# FetherV2_REV1.net
KiCad netlist of a schematic drawn in EAGLE
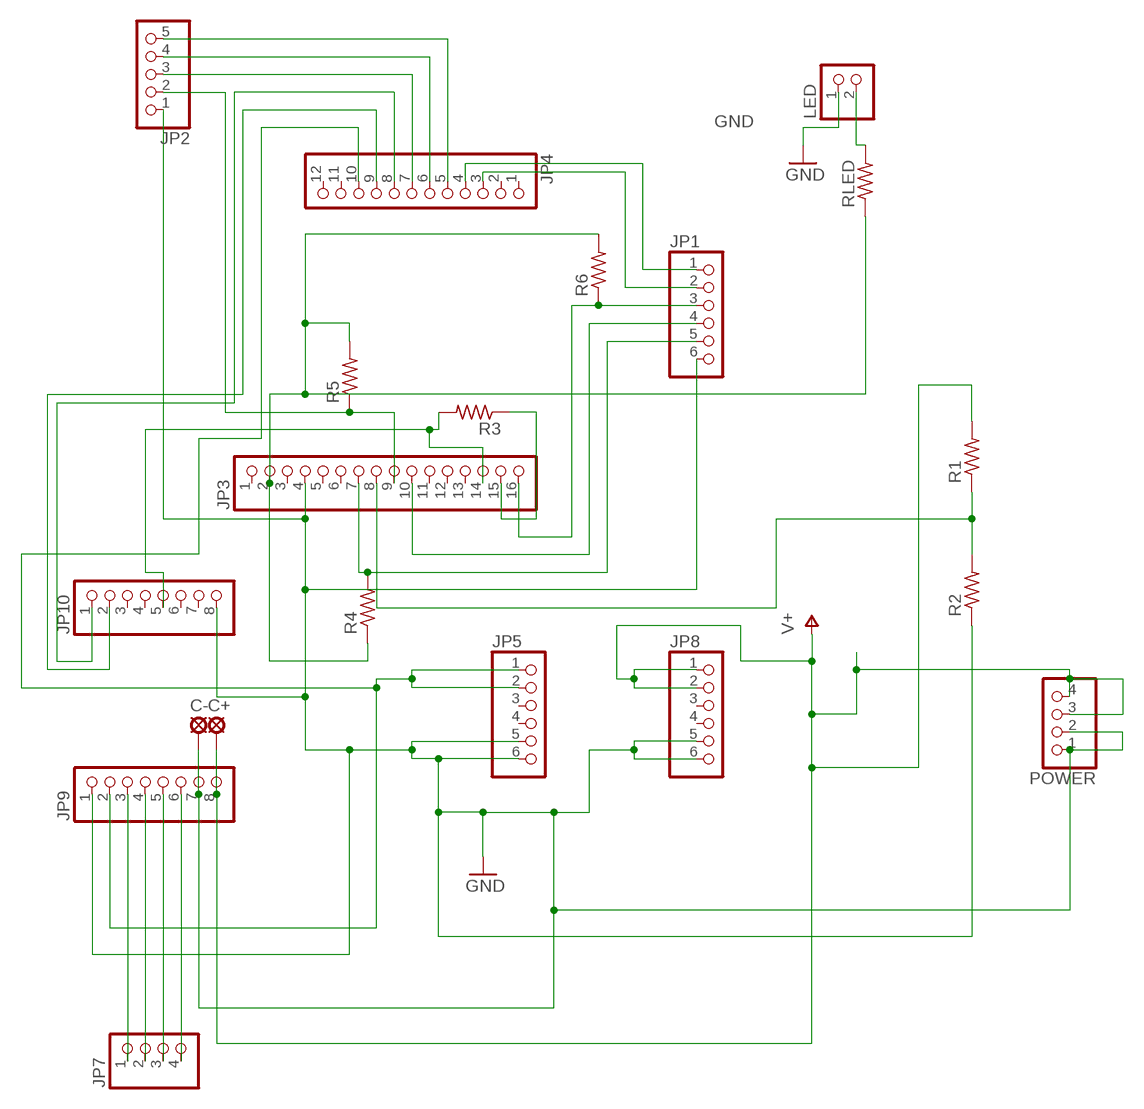
[diagram p0: schematic, sheet 1]

(export (version "E")
  (design (tool "Eeschema 10.0.6"))
  (components
    (comp (ref "C+")
      (value "SE14")
      (footprint "eagle-import:SE14")
      (libsource (lib "eagle-import") (part "SE14"))
    )
    (comp (ref "C-")
      (value "SE14")
      (footprint "eagle-import:SE14")
      (libsource (lib "eagle-import") (part "SE14"))
    )
    (comp (ref "JP1")
      (value "PINHD-1X6/90")
      (footprint "eagle-import:1X06_90")
      (libsource (lib "eagle-import") (part "PINHD-1X6/90"))
    )
    (comp (ref "JP2")
      (value "PINHD-1X5/90")
      (footprint "eagle-import:1X05_90")
      (libsource (lib "eagle-import") (part "PINHD-1X5/90"))
    )
    (comp (ref "JP3")
      (value "PINHD-1X16")
      (footprint "eagle-import:1X16")
      (libsource (lib "eagle-import") (part "PINHD-1X16"))
    )
    (comp (ref "JP4")
      (value "PINHD-1X12")
      (footprint "eagle-import:1X12")
      (libsource (lib "eagle-import") (part "PINHD-1X12"))
    )
    (comp (ref "JP5")
      (value "PINHD-1X6")
      (footprint "eagle-import:1X06")
      (libsource (lib "eagle-import") (part "PINHD-1X6"))
    )
    (comp (ref "JP7")
      (value "PINHD-1X4")
      (footprint "eagle-import:1X04")
      (libsource (lib "eagle-import") (part "PINHD-1X4"))
    )
    (comp (ref "JP8")
      (value "PINHD-1X6")
      (footprint "eagle-import:1X06")
      (libsource (lib "eagle-import") (part "PINHD-1X6"))
    )
    (comp (ref "JP9")
      (value "PINHD-1X8")
      (footprint "eagle-import:1X08")
      (libsource (lib "eagle-import") (part "PINHD-1X8"))
    )
    (comp (ref "JP10")
      (value "PINHD-1X8")
      (footprint "eagle-import:1X08")
      (libsource (lib "eagle-import") (part "PINHD-1X8"))
    )
    (comp (ref "LED")
      (value "PINHD-1X2")
      (footprint "eagle-import:1X02")
      (libsource (lib "eagle-import") (part "PINHD-1X2"))
    )
    (comp (ref "POWER")
      (value "PINHD-1X4")
      (footprint "eagle-import:1X04")
      (libsource (lib "eagle-import") (part "PINHD-1X4"))
    )
    (comp (ref "R1")
      (value "FLIPFLOP-RES")
      (footprint "eagle-import:0805-THM")
      (libsource (lib "eagle-import") (part "FLIPFLOP-RES"))
    )
    (comp (ref "R2")
      (value "FLIPFLOP-RES")
      (footprint "eagle-import:0805-THM")
      (libsource (lib "eagle-import") (part "FLIPFLOP-RES"))
    )
    (comp (ref "R3")
      (value "FLIPFLOP-RES")
      (footprint "eagle-import:0805-THM")
      (libsource (lib "eagle-import") (part "FLIPFLOP-RES"))
    )
    (comp (ref "R4")
      (value "FLIPFLOP-RES")
      (footprint "eagle-import:0805-THM")
      (libsource (lib "eagle-import") (part "FLIPFLOP-RES"))
    )
    (comp (ref "R5")
      (value "FLIPFLOP-RES")
      (footprint "eagle-import:0805-THM")
      (libsource (lib "eagle-import") (part "FLIPFLOP-RES"))
    )
    (comp (ref "R6")
      (value "FLIPFLOP-RES")
      (footprint "eagle-import:0805-THM")
      (libsource (lib "eagle-import") (part "FLIPFLOP-RES"))
    )
    (comp (ref "RLED")
      (value "FLIPFLOP-RES")
      (footprint "eagle-import:0805-THM")
      (libsource (lib "eagle-import") (part "FLIPFLOP-RES"))
    )
  )
  (nets
    (net (code "1") (name "GND") (class "Default")
      (node (ref "C-") (pin "MP") (pinfunction "MP_MP") (pintype "passive"))
      (node (ref "JP1") (pin "6") (pinfunction "6_6") (pintype "passive"))
      (node (ref "JP10") (pin "8") (pinfunction "8_8") (pintype "passive"))
      (node (ref "JP2") (pin "1") (pinfunction "1_1") (pintype "passive"))
      (node (ref "JP3") (pin "4") (pinfunction "4_4") (pintype "passive"))
      (node (ref "JP5") (pin "5") (pinfunction "5_5") (pintype "passive"))
      (node (ref "JP5") (pin "6") (pinfunction "6_6") (pintype "passive"))
      (node (ref "JP8") (pin "5") (pinfunction "5_5") (pintype "passive"))
      (node (ref "JP8") (pin "6") (pinfunction "6_6") (pintype "passive"))
      (node (ref "JP9") (pin "1") (pinfunction "1_1") (pintype "passive"))
      (node (ref "JP9") (pin "7") (pinfunction "7_7") (pintype "passive"))
      (node (ref "LED") (pin "1") (pinfunction "1_1") (pintype "passive"))
      (node (ref "POWER") (pin "1") (pinfunction "1_1") (pintype "passive"))
      (node (ref "POWER") (pin "2") (pinfunction "2_2") (pintype "passive"))
      (node (ref "R2") (pin "1") (pinfunction "1_1") (pintype "passive"))
    )
    (net (code "2") (name "Net-(JP1-Pad1)") (class "Default")
      (node (ref "JP1") (pin "1") (pinfunction "1_1") (pintype "passive"))
      (node (ref "JP4") (pin "4") (pinfunction "4_4") (pintype "passive"))
    )
    (net (code "3") (name "Net-(JP1-Pad2)") (class "Default")
      (node (ref "JP1") (pin "2") (pinfunction "2_2") (pintype "passive"))
      (node (ref "JP4") (pin "3") (pinfunction "3_3") (pintype "passive"))
    )
    (net (code "4") (name "Net-(JP1-Pad3)") (class "Default")
      (node (ref "JP1") (pin "3") (pinfunction "3_3") (pintype "passive"))
      (node (ref "JP3") (pin "16") (pinfunction "16_16") (pintype "passive"))
      (node (ref "R6") (pin "1") (pinfunction "1_1") (pintype "passive"))
    )
    (net (code "5") (name "Net-(JP1-Pad4)") (class "Default")
      (node (ref "JP1") (pin "4") (pinfunction "4_4") (pintype "passive"))
      (node (ref "JP3") (pin "10") (pinfunction "10_10") (pintype "passive"))
    )
    (net (code "6") (name "Net-(JP1-Pad5)") (class "Default")
      (node (ref "JP1") (pin "5") (pinfunction "5_5") (pintype "passive"))
      (node (ref "JP3") (pin "7") (pinfunction "7_7") (pintype "passive"))
      (node (ref "R4") (pin "2") (pinfunction "2_2") (pintype "passive"))
    )
    (net (code "7") (name "Net-(JP2-Pad2)") (class "Default")
      (node (ref "JP2") (pin "2") (pinfunction "2_2") (pintype "passive"))
      (node (ref "JP3") (pin "9") (pinfunction "9_9") (pintype "passive"))
      (node (ref "R5") (pin "1") (pinfunction "1_1") (pintype "passive"))
    )
    (net (code "8") (name "Net-(JP2-Pad3)") (class "Default")
      (node (ref "JP2") (pin "3") (pinfunction "3_3") (pintype "passive"))
      (node (ref "JP4") (pin "7") (pinfunction "7_7") (pintype "passive"))
    )
    (net (code "9") (name "Net-(JP2-Pad4)") (class "Default")
      (node (ref "JP2") (pin "4") (pinfunction "4_4") (pintype "passive"))
      (node (ref "JP4") (pin "6") (pinfunction "6_6") (pintype "passive"))
    )
    (net (code "10") (name "Net-(JP2-Pad5)") (class "Default")
      (node (ref "JP2") (pin "5") (pinfunction "5_5") (pintype "passive"))
      (node (ref "JP4") (pin "5") (pinfunction "5_5") (pintype "passive"))
    )
    (net (code "11") (name "Net-(JP3-Pad2)") (class "Default")
      (node (ref "JP3") (pin "2") (pinfunction "2_2") (pintype "passive"))
      (node (ref "R4") (pin "1") (pinfunction "1_1") (pintype "passive"))
      (node (ref "R5") (pin "2") (pinfunction "2_2") (pintype "passive"))
      (node (ref "R6") (pin "2") (pinfunction "2_2") (pintype "passive"))
      (node (ref "RLED") (pin "1") (pinfunction "1_1") (pintype "passive"))
    )
    (net (code "12") (name "Net-(JP3-Pad8)") (class "Default")
      (node (ref "JP3") (pin "8") (pinfunction "8_8") (pintype "passive"))
      (node (ref "R1") (pin "1") (pinfunction "1_1") (pintype "passive"))
      (node (ref "R2") (pin "2") (pinfunction "2_2") (pintype "passive"))
    )
    (net (code "13") (name "Net-(JP3-Pad15)") (class "Default")
      (node (ref "JP3") (pin "15") (pinfunction "15_15") (pintype "passive"))
      (node (ref "R3") (pin "1") (pinfunction "1_1") (pintype "passive"))
    )
    (net (code "14") (name "Net-(JP4-Pad10)") (class "Default")
      (node (ref "JP4") (pin "10") (pinfunction "10_10") (pintype "passive"))
      (node (ref "JP5") (pin "1") (pinfunction "1_1") (pintype "passive"))
      (node (ref "JP5") (pin "2") (pinfunction "2_2") (pintype "passive"))
      (node (ref "JP9") (pin "2") (pinfunction "2_2") (pintype "passive"))
    )
    (net (code "15") (name "Net-(JP7-Pad1)") (class "Default")
      (node (ref "JP7") (pin "1") (pinfunction "1_1") (pintype "passive"))
      (node (ref "JP9") (pin "3") (pinfunction "3_3") (pintype "passive"))
    )
    (net (code "16") (name "Net-(JP7-Pad2)") (class "Default")
      (node (ref "JP7") (pin "2") (pinfunction "2_2") (pintype "passive"))
      (node (ref "JP9") (pin "4") (pinfunction "4_4") (pintype "passive"))
    )
    (net (code "17") (name "Net-(JP7-Pad3)") (class "Default")
      (node (ref "JP7") (pin "3") (pinfunction "3_3") (pintype "passive"))
      (node (ref "JP9") (pin "5") (pinfunction "5_5") (pintype "passive"))
    )
    (net (code "18") (name "Net-(JP7-Pad4)") (class "Default")
      (node (ref "JP7") (pin "4") (pinfunction "4_4") (pintype "passive"))
      (node (ref "JP9") (pin "6") (pinfunction "6_6") (pintype "passive"))
    )
    (net (code "19") (name "Net-(JP10-Pad1)") (class "Default")
      (node (ref "JP10") (pin "1") (pinfunction "1_1") (pintype "passive"))
      (node (ref "JP4") (pin "8") (pinfunction "8_8") (pintype "passive"))
    )
    (net (code "20") (name "Net-(JP10-Pad2)") (class "Default")
      (node (ref "JP10") (pin "2") (pinfunction "2_2") (pintype "passive"))
      (node (ref "JP4") (pin "9") (pinfunction "9_9") (pintype "passive"))
    )
    (net (code "21") (name "Net-(JP10-Pad5)") (class "Default")
      (node (ref "JP10") (pin "5") (pinfunction "5_5") (pintype "passive"))
      (node (ref "JP3") (pin "14") (pinfunction "14_14") (pintype "passive"))
      (node (ref "R3") (pin "2") (pinfunction "2_2") (pintype "passive"))
    )
    (net (code "22") (name "Net-(LED-Pad2)") (class "Default")
      (node (ref "LED") (pin "2") (pinfunction "2_2") (pintype "passive"))
      (node (ref "RLED") (pin "2") (pinfunction "2_2") (pintype "passive"))
    )
    (net (code "23") (name "V+") (class "Default")
      (node (ref "C+") (pin "MP") (pinfunction "MP_MP") (pintype "passive"))
      (node (ref "JP8") (pin "1") (pinfunction "1_1") (pintype "passive"))
      (node (ref "JP8") (pin "2") (pinfunction "2_2") (pintype "passive"))
      (node (ref "JP9") (pin "8") (pinfunction "8_8") (pintype "passive"))
      (node (ref "POWER") (pin "3") (pinfunction "3_3") (pintype "passive"))
      (node (ref "POWER") (pin "4") (pinfunction "4_4") (pintype "passive"))
      (node (ref "R1") (pin "2") (pinfunction "2_2") (pintype "passive"))
    )
    (net (code "24") (name "unconnected-(JP3-Pad1)") (class "Default")
      (node (ref "JP3") (pin "1") (pinfunction "1_1") (pintype "passive"))
    )
    (net (code "25") (name "unconnected-(JP3-Pad3)") (class "Default")
      (node (ref "JP3") (pin "3") (pinfunction "3_3") (pintype "passive"))
    )
    (net (code "26") (name "unconnected-(JP3-Pad5)") (class "Default")
      (node (ref "JP3") (pin "5") (pinfunction "5_5") (pintype "passive"))
    )
    (net (code "27") (name "unconnected-(JP3-Pad6)") (class "Default")
      (node (ref "JP3") (pin "6") (pinfunction "6_6") (pintype "passive"))
    )
    (net (code "28") (name "unconnected-(JP3-Pad11)") (class "Default")
      (node (ref "JP3") (pin "11") (pinfunction "11_11") (pintype "passive"))
    )
    (net (code "29") (name "unconnected-(JP3-Pad12)") (class "Default")
      (node (ref "JP3") (pin "12") (pinfunction "12_12") (pintype "passive"))
    )
    (net (code "30") (name "unconnected-(JP3-Pad13)") (class "Default")
      (node (ref "JP3") (pin "13") (pinfunction "13_13") (pintype "passive"))
    )
    (net (code "31") (name "unconnected-(JP4-Pad1)") (class "Default")
      (node (ref "JP4") (pin "1") (pinfunction "1_1") (pintype "passive"))
    )
    (net (code "32") (name "unconnected-(JP4-Pad2)") (class "Default")
      (node (ref "JP4") (pin "2") (pinfunction "2_2") (pintype "passive"))
    )
    (net (code "33") (name "unconnected-(JP4-Pad11)") (class "Default")
      (node (ref "JP4") (pin "11") (pinfunction "11_11") (pintype "passive"))
    )
    (net (code "34") (name "unconnected-(JP4-Pad12)") (class "Default")
      (node (ref "JP4") (pin "12") (pinfunction "12_12") (pintype "passive"))
    )
    (net (code "35") (name "unconnected-(JP5-Pad3)") (class "Default")
      (node (ref "JP5") (pin "3") (pinfunction "3_3") (pintype "passive"))
    )
    (net (code "36") (name "unconnected-(JP5-Pad4)") (class "Default")
      (node (ref "JP5") (pin "4") (pinfunction "4_4") (pintype "passive"))
    )
    (net (code "37") (name "unconnected-(JP8-Pad3)") (class "Default")
      (node (ref "JP8") (pin "3") (pinfunction "3_3") (pintype "passive"))
    )
    (net (code "38") (name "unconnected-(JP8-Pad4)") (class "Default")
      (node (ref "JP8") (pin "4") (pinfunction "4_4") (pintype "passive"))
    )
    (net (code "39") (name "unconnected-(JP10-Pad3)") (class "Default")
      (node (ref "JP10") (pin "3") (pinfunction "3_3") (pintype "passive"))
    )
    (net (code "40") (name "unconnected-(JP10-Pad4)") (class "Default")
      (node (ref "JP10") (pin "4") (pinfunction "4_4") (pintype "passive"))
    )
    (net (code "41") (name "unconnected-(JP10-Pad6)") (class "Default")
      (node (ref "JP10") (pin "6") (pinfunction "6_6") (pintype "passive"))
    )
    (net (code "42") (name "unconnected-(JP10-Pad7)") (class "Default")
      (node (ref "JP10") (pin "7") (pinfunction "7_7") (pintype "passive"))
    )
  )
)
